# LED_board.net
KiCad netlist of a schematic drawn in EAGLE
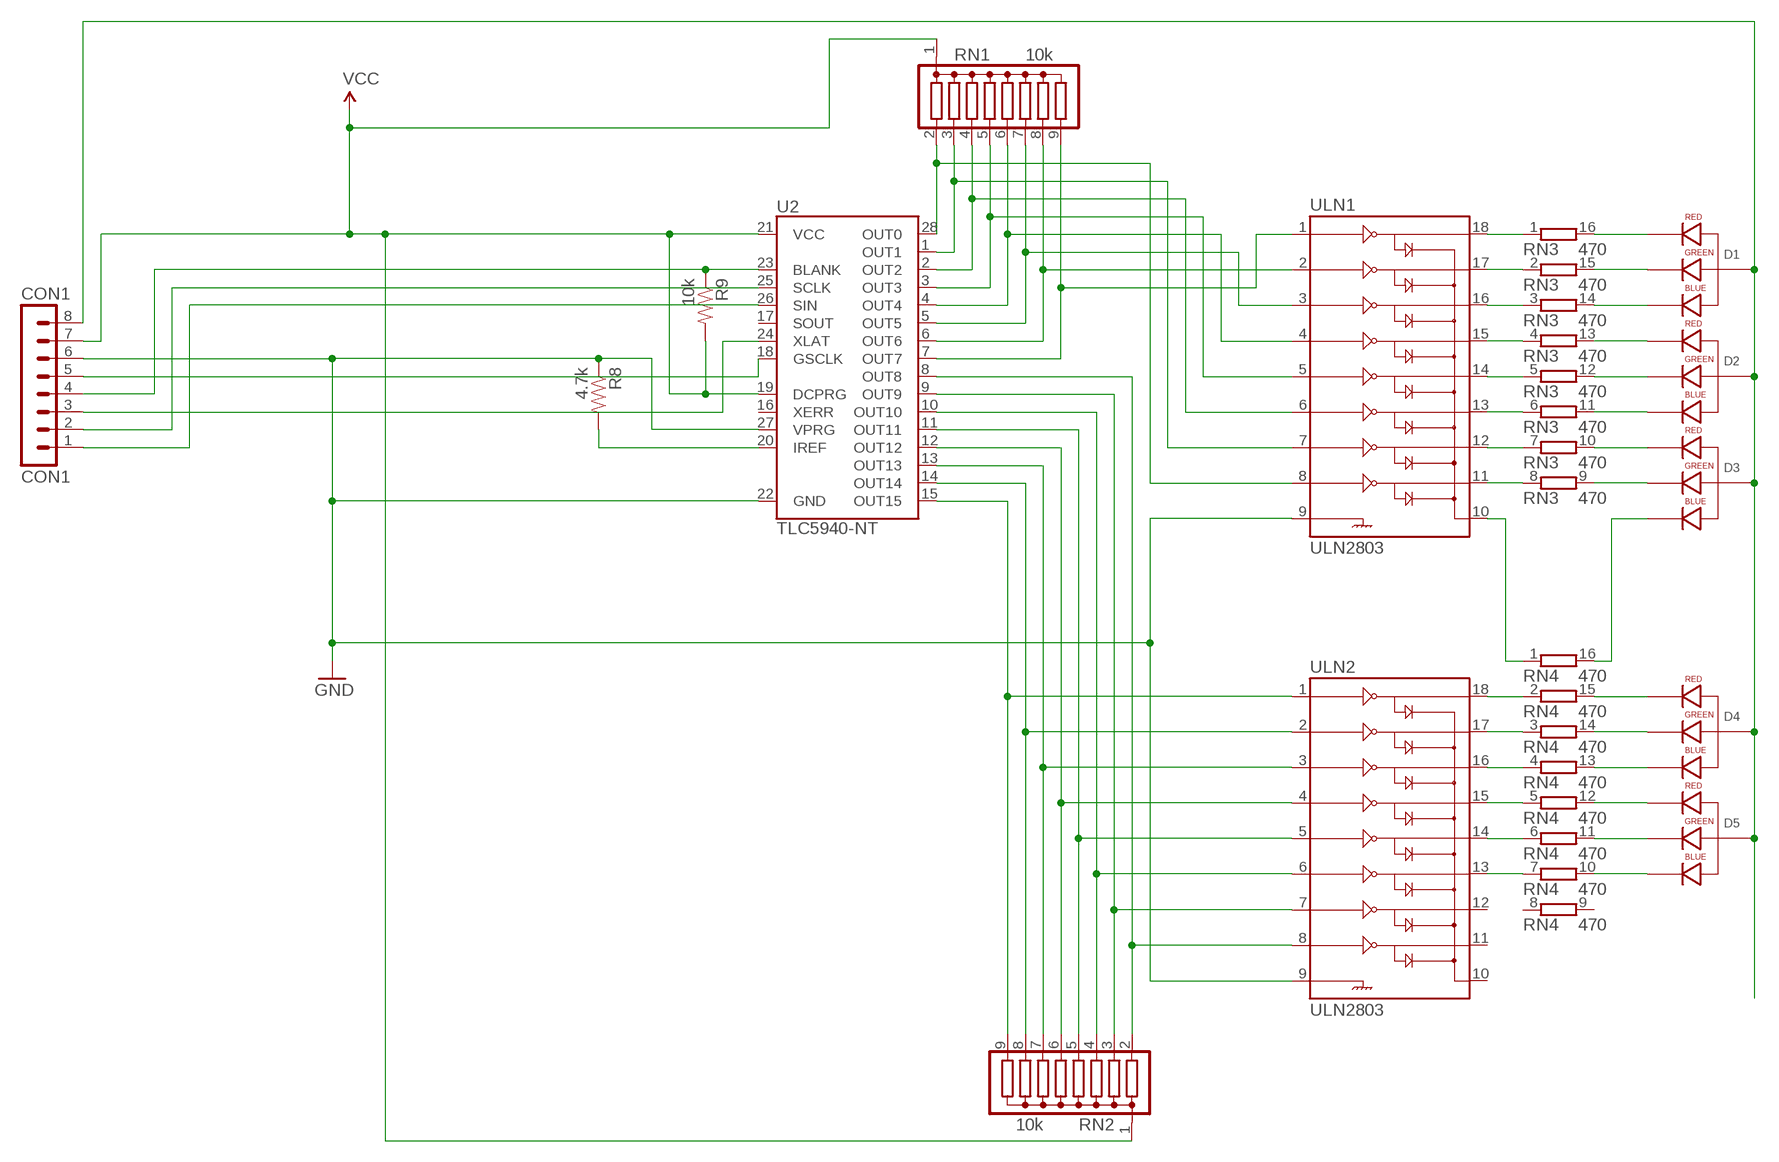
[diagram p0: schematic, sheet 1]

(export (version "E")
  (design (tool "Eeschema 10.0.6"))
  (components
    (comp (ref "CON1")
      (value "CON1")
      (footprint "eagle-import:MA08-1")
      (libsource (lib "eagle-import") (part "MA08-1"))
    )
    (comp (ref "D1")
      (value "LED-RGB-CA-THRUCLEAR")
      (footprint "eagle-import:LED-RGB-THRU")
      (libsource (lib "eagle-import") (part "LED-RGB-CA-THRUCLEAR"))
    )
    (comp (ref "D2")
      (value "LED-RGB-CA-THRUCLEAR")
      (footprint "eagle-import:LED-RGB-THRU")
      (libsource (lib "eagle-import") (part "LED-RGB-CA-THRUCLEAR"))
    )
    (comp (ref "D3")
      (value "LED-RGB-CA-THRUCLEAR")
      (footprint "eagle-import:LED-RGB-THRU")
      (libsource (lib "eagle-import") (part "LED-RGB-CA-THRUCLEAR"))
    )
    (comp (ref "D4")
      (value "LED-RGB-CA-THRUCLEAR")
      (footprint "eagle-import:LED-RGB-THRU")
      (libsource (lib "eagle-import") (part "LED-RGB-CA-THRUCLEAR"))
    )
    (comp (ref "D5")
      (value "LED-RGB-CA-THRUCLEAR")
      (footprint "eagle-import:LED-RGB-THRU")
      (libsource (lib "eagle-import") (part "LED-RGB-CA-THRUCLEAR"))
    )
    (comp (ref "R8")
      (value "4.7k")
      (footprint "eagle-import:AXIAL-0.5")
      (libsource (lib "eagle-import") (part "RESISTORPTH-1/2W"))
    )
    (comp (ref "R9")
      (value "10k")
      (footprint "eagle-import:AXIAL-0.5")
      (libsource (lib "eagle-import") (part "RESISTORPTH-1/2W"))
    )
    (comp (ref "RN1")
      (value "10k")
      (footprint "eagle-import:SIL9")
      (libsource (lib "eagle-import") (part "G08R"))
    )
    (comp (ref "RN2")
      (value "10k")
      (footprint "eagle-import:SIL9")
      (libsource (lib "eagle-import") (part "G08R"))
    )
    (comp (ref "RN3")
      (value "470")
      (footprint "eagle-import:DIL16")
      (libsource (lib "eagle-import") (part "8R-P"))
    )
    (comp (ref "RN4")
      (value "470")
      (footprint "eagle-import:DIL16")
      (libsource (lib "eagle-import") (part "8R-P"))
    )
    (comp (ref "U2")
      (value "TLC5940-NT")
      (footprint "eagle-import:DIL28-3")
      (libsource (lib "eagle-import") (part "TLC5940-NT"))
    )
    (comp (ref "ULN1")
      (value "ULN2803")
      (footprint "eagle-import:DIL18")
      (libsource (lib "eagle-import") (part "ULN2803DIP"))
    )
    (comp (ref "ULN2")
      (value "ULN2803")
      (footprint "eagle-import:DIL18")
      (libsource (lib "eagle-import") (part "ULN2803DIP"))
    )
  )
  (nets
    (net (code "1") (name "GND") (class "Default")
      (node (ref "CON1") (pin "6") (pinfunction "6_6") (pintype "passive"))
      (node (ref "R8") (pin "P$1") (pinfunction "1_P$1") (pintype "passive"))
      (node (ref "U2") (pin "22") (pinfunction "GND_22") (pintype "bidirectional"))
      (node (ref "U2") (pin "27") (pinfunction "VPRG_27") (pintype "bidirectional"))
      (node (ref "ULN1") (pin "9") (pinfunction "9_9") (pintype "bidirectional"))
      (node (ref "ULN2") (pin "9") (pinfunction "9_9") (pintype "bidirectional"))
    )
    (net (code "2") (name "Net-(D1-ANODE)") (class "Default")
      (node (ref "CON1") (pin "8") (pinfunction "8_8") (pintype "passive"))
      (node (ref "D1") (pin "2") (pinfunction "ANODE_2") (pintype "bidirectional"))
      (node (ref "D2") (pin "2") (pinfunction "ANODE_2") (pintype "bidirectional"))
      (node (ref "D3") (pin "2") (pinfunction "ANODE_2") (pintype "bidirectional"))
      (node (ref "D4") (pin "2") (pinfunction "ANODE_2") (pintype "bidirectional"))
      (node (ref "D5") (pin "2") (pinfunction "ANODE_2") (pintype "bidirectional"))
    )
    (net (code "3") (name "Net-(D1-BLUE_CATHODE)") (class "Default")
      (node (ref "D1") (pin "4") (pinfunction "BLUE_CATHODE_4") (pintype "bidirectional"))
      (node (ref "RN3") (pin "14") (pinfunction "2_14") (pintype "passive"))
    )
    (net (code "4") (name "Net-(D1-GREEN_CATHODE)") (class "Default")
      (node (ref "D1") (pin "3") (pinfunction "GREEN_CATHODE_3") (pintype "bidirectional"))
      (node (ref "RN3") (pin "15") (pinfunction "2_15") (pintype "passive"))
    )
    (net (code "5") (name "Net-(D1-RED_CATHODE)") (class "Default")
      (node (ref "D1") (pin "1") (pinfunction "RED_CATHODE_1") (pintype "bidirectional"))
      (node (ref "RN3") (pin "16") (pinfunction "2_16") (pintype "passive"))
    )
    (net (code "6") (name "Net-(D2-BLUE_CATHODE)") (class "Default")
      (node (ref "D2") (pin "4") (pinfunction "BLUE_CATHODE_4") (pintype "bidirectional"))
      (node (ref "RN3") (pin "11") (pinfunction "2_11") (pintype "passive"))
    )
    (net (code "7") (name "Net-(D2-GREEN_CATHODE)") (class "Default")
      (node (ref "D2") (pin "3") (pinfunction "GREEN_CATHODE_3") (pintype "bidirectional"))
      (node (ref "RN3") (pin "12") (pinfunction "2_12") (pintype "passive"))
    )
    (net (code "8") (name "Net-(D2-RED_CATHODE)") (class "Default")
      (node (ref "D2") (pin "1") (pinfunction "RED_CATHODE_1") (pintype "bidirectional"))
      (node (ref "RN3") (pin "13") (pinfunction "2_13") (pintype "passive"))
    )
    (net (code "9") (name "Net-(D3-BLUE_CATHODE)") (class "Default")
      (node (ref "D3") (pin "4") (pinfunction "BLUE_CATHODE_4") (pintype "bidirectional"))
      (node (ref "RN4") (pin "16") (pinfunction "2_16") (pintype "passive"))
    )
    (net (code "10") (name "Net-(D3-GREEN_CATHODE)") (class "Default")
      (node (ref "D3") (pin "3") (pinfunction "GREEN_CATHODE_3") (pintype "bidirectional"))
      (node (ref "RN3") (pin "9") (pinfunction "2_9") (pintype "passive"))
    )
    (net (code "11") (name "Net-(D3-RED_CATHODE)") (class "Default")
      (node (ref "D3") (pin "1") (pinfunction "RED_CATHODE_1") (pintype "bidirectional"))
      (node (ref "RN3") (pin "10") (pinfunction "2_10") (pintype "passive"))
    )
    (net (code "12") (name "Net-(D4-BLUE_CATHODE)") (class "Default")
      (node (ref "D4") (pin "4") (pinfunction "BLUE_CATHODE_4") (pintype "bidirectional"))
      (node (ref "RN4") (pin "13") (pinfunction "2_13") (pintype "passive"))
    )
    (net (code "13") (name "Net-(D4-GREEN_CATHODE)") (class "Default")
      (node (ref "D4") (pin "3") (pinfunction "GREEN_CATHODE_3") (pintype "bidirectional"))
      (node (ref "RN4") (pin "14") (pinfunction "2_14") (pintype "passive"))
    )
    (net (code "14") (name "Net-(D4-RED_CATHODE)") (class "Default")
      (node (ref "D4") (pin "1") (pinfunction "RED_CATHODE_1") (pintype "bidirectional"))
      (node (ref "RN4") (pin "15") (pinfunction "2_15") (pintype "passive"))
    )
    (net (code "15") (name "Net-(D5-BLUE_CATHODE)") (class "Default")
      (node (ref "D5") (pin "4") (pinfunction "BLUE_CATHODE_4") (pintype "bidirectional"))
      (node (ref "RN4") (pin "10") (pinfunction "2_10") (pintype "passive"))
    )
    (net (code "16") (name "Net-(D5-GREEN_CATHODE)") (class "Default")
      (node (ref "D5") (pin "3") (pinfunction "GREEN_CATHODE_3") (pintype "bidirectional"))
      (node (ref "RN4") (pin "11") (pinfunction "2_11") (pintype "passive"))
    )
    (net (code "17") (name "Net-(D5-RED_CATHODE)") (class "Default")
      (node (ref "D5") (pin "1") (pinfunction "RED_CATHODE_1") (pintype "bidirectional"))
      (node (ref "RN4") (pin "12") (pinfunction "2_12") (pintype "passive"))
    )
    (net (code "18") (name "Net-(R8-2)") (class "Default")
      (node (ref "R8") (pin "P$2") (pinfunction "2_P$2") (pintype "passive"))
      (node (ref "U2") (pin "20") (pinfunction "IREF_20") (pintype "bidirectional"))
    )
    (net (code "19") (name "Net-(R9-1)") (class "Default")
      (node (ref "CON1") (pin "4") (pinfunction "4_4") (pintype "passive"))
      (node (ref "R9") (pin "P$1") (pinfunction "1_P$1") (pintype "passive"))
      (node (ref "U2") (pin "23") (pinfunction "BLANK_23") (pintype "bidirectional"))
    )
    (net (code "20") (name "Net-(RN3-Pad1)") (class "Default")
      (node (ref "RN3") (pin "1") (pinfunction "1_1") (pintype "passive"))
      (node (ref "ULN1") (pin "18") (pinfunction "18_18") (pintype "bidirectional"))
    )
    (net (code "21") (name "Net-(RN3B-1)") (class "Default")
      (node (ref "RN3") (pin "2") (pinfunction "1_2") (pintype "passive"))
      (node (ref "ULN1") (pin "17") (pinfunction "17_17") (pintype "bidirectional"))
    )
    (net (code "22") (name "Net-(RN3C-1)") (class "Default")
      (node (ref "RN3") (pin "3") (pinfunction "1_3") (pintype "passive"))
      (node (ref "ULN1") (pin "16") (pinfunction "16_16") (pintype "bidirectional"))
    )
    (net (code "23") (name "Net-(RN3D-1)") (class "Default")
      (node (ref "RN3") (pin "4") (pinfunction "1_4") (pintype "passive"))
      (node (ref "ULN1") (pin "15") (pinfunction "15_15") (pintype "bidirectional"))
    )
    (net (code "24") (name "Net-(RN3E-1)") (class "Default")
      (node (ref "RN3") (pin "5") (pinfunction "1_5") (pintype "passive"))
      (node (ref "ULN1") (pin "14") (pinfunction "14_14") (pintype "bidirectional"))
    )
    (net (code "25") (name "Net-(RN3F-1)") (class "Default")
      (node (ref "RN3") (pin "6") (pinfunction "1_6") (pintype "passive"))
      (node (ref "ULN1") (pin "13") (pinfunction "13_13") (pintype "bidirectional"))
    )
    (net (code "26") (name "Net-(RN3G-1)") (class "Default")
      (node (ref "RN3") (pin "7") (pinfunction "1_7") (pintype "passive"))
      (node (ref "ULN1") (pin "12") (pinfunction "12_12") (pintype "bidirectional"))
    )
    (net (code "27") (name "Net-(RN3H-1)") (class "Default")
      (node (ref "RN3") (pin "8") (pinfunction "1_8") (pintype "passive"))
      (node (ref "ULN1") (pin "11") (pinfunction "11_11") (pintype "bidirectional"))
    )
    (net (code "28") (name "Net-(RN4-Pad1)") (class "Default")
      (node (ref "RN4") (pin "1") (pinfunction "1_1") (pintype "passive"))
      (node (ref "ULN1") (pin "10") (pinfunction "10_10") (pintype "bidirectional"))
    )
    (net (code "29") (name "Net-(RN4B-1)") (class "Default")
      (node (ref "RN4") (pin "2") (pinfunction "1_2") (pintype "passive"))
      (node (ref "ULN2") (pin "18") (pinfunction "18_18") (pintype "bidirectional"))
    )
    (net (code "30") (name "Net-(RN4C-1)") (class "Default")
      (node (ref "RN4") (pin "3") (pinfunction "1_3") (pintype "passive"))
      (node (ref "ULN2") (pin "17") (pinfunction "17_17") (pintype "bidirectional"))
    )
    (net (code "31") (name "Net-(RN4D-1)") (class "Default")
      (node (ref "RN4") (pin "4") (pinfunction "1_4") (pintype "passive"))
      (node (ref "ULN2") (pin "16") (pinfunction "16_16") (pintype "bidirectional"))
    )
    (net (code "32") (name "Net-(RN4E-1)") (class "Default")
      (node (ref "RN4") (pin "5") (pinfunction "1_5") (pintype "passive"))
      (node (ref "ULN2") (pin "15") (pinfunction "15_15") (pintype "bidirectional"))
    )
    (net (code "33") (name "Net-(RN4F-1)") (class "Default")
      (node (ref "RN4") (pin "6") (pinfunction "1_6") (pintype "passive"))
      (node (ref "ULN2") (pin "14") (pinfunction "14_14") (pintype "bidirectional"))
    )
    (net (code "34") (name "Net-(RN4G-1)") (class "Default")
      (node (ref "RN4") (pin "7") (pinfunction "1_7") (pintype "passive"))
      (node (ref "ULN2") (pin "13") (pinfunction "13_13") (pintype "bidirectional"))
    )
    (net (code "35") (name "Net-(U2-GSCLK)") (class "Default")
      (node (ref "CON1") (pin "5") (pinfunction "5_5") (pintype "passive"))
      (node (ref "U2") (pin "18") (pinfunction "GSCLK_18") (pintype "bidirectional"))
    )
    (net (code "36") (name "Net-(U2-OUT0)") (class "Default")
      (node (ref "RN1") (pin "2") (pinfunction "2_2") (pintype "passive"))
      (node (ref "U2") (pin "28") (pinfunction "OUT0_28") (pintype "bidirectional"))
      (node (ref "ULN1") (pin "8") (pinfunction "8_8") (pintype "bidirectional"))
    )
    (net (code "37") (name "Net-(U2-OUT1)") (class "Default")
      (node (ref "RN1") (pin "3") (pinfunction "3_3") (pintype "passive"))
      (node (ref "U2") (pin "1") (pinfunction "OUT1_1") (pintype "bidirectional"))
      (node (ref "ULN1") (pin "7") (pinfunction "7_7") (pintype "bidirectional"))
    )
    (net (code "38") (name "Net-(U2-OUT2)") (class "Default")
      (node (ref "RN1") (pin "4") (pinfunction "4_4") (pintype "passive"))
      (node (ref "U2") (pin "2") (pinfunction "OUT2_2") (pintype "bidirectional"))
      (node (ref "ULN1") (pin "6") (pinfunction "6_6") (pintype "bidirectional"))
    )
    (net (code "39") (name "Net-(U2-OUT3)") (class "Default")
      (node (ref "RN1") (pin "5") (pinfunction "5_5") (pintype "passive"))
      (node (ref "U2") (pin "3") (pinfunction "OUT3_3") (pintype "bidirectional"))
      (node (ref "ULN1") (pin "5") (pinfunction "5_5") (pintype "bidirectional"))
    )
    (net (code "40") (name "Net-(U2-OUT4)") (class "Default")
      (node (ref "RN1") (pin "6") (pinfunction "6_6") (pintype "passive"))
      (node (ref "U2") (pin "4") (pinfunction "OUT4_4") (pintype "bidirectional"))
      (node (ref "ULN1") (pin "4") (pinfunction "4_4") (pintype "bidirectional"))
    )
    (net (code "41") (name "Net-(U2-OUT5)") (class "Default")
      (node (ref "RN1") (pin "7") (pinfunction "7_7") (pintype "passive"))
      (node (ref "U2") (pin "5") (pinfunction "OUT5_5") (pintype "bidirectional"))
      (node (ref "ULN1") (pin "3") (pinfunction "3_3") (pintype "bidirectional"))
    )
    (net (code "42") (name "Net-(U2-OUT6)") (class "Default")
      (node (ref "RN1") (pin "8") (pinfunction "8_8") (pintype "passive"))
      (node (ref "U2") (pin "6") (pinfunction "OUT6_6") (pintype "bidirectional"))
      (node (ref "ULN1") (pin "2") (pinfunction "2_2") (pintype "bidirectional"))
    )
    (net (code "43") (name "Net-(U2-OUT7)") (class "Default")
      (node (ref "RN1") (pin "9") (pinfunction "9_9") (pintype "passive"))
      (node (ref "U2") (pin "7") (pinfunction "OUT7_7") (pintype "bidirectional"))
      (node (ref "ULN1") (pin "1") (pinfunction "1_1") (pintype "bidirectional"))
    )
    (net (code "44") (name "Net-(U2-OUT8)") (class "Default")
      (node (ref "RN2") (pin "2") (pinfunction "2_2") (pintype "passive"))
      (node (ref "U2") (pin "8") (pinfunction "OUT8_8") (pintype "bidirectional"))
      (node (ref "ULN2") (pin "8") (pinfunction "8_8") (pintype "bidirectional"))
    )
    (net (code "45") (name "Net-(U2-OUT9)") (class "Default")
      (node (ref "RN2") (pin "3") (pinfunction "3_3") (pintype "passive"))
      (node (ref "U2") (pin "9") (pinfunction "OUT9_9") (pintype "bidirectional"))
      (node (ref "ULN2") (pin "7") (pinfunction "7_7") (pintype "bidirectional"))
    )
    (net (code "46") (name "Net-(U2-OUT10)") (class "Default")
      (node (ref "RN2") (pin "4") (pinfunction "4_4") (pintype "passive"))
      (node (ref "U2") (pin "10") (pinfunction "OUT10_10") (pintype "bidirectional"))
      (node (ref "ULN2") (pin "6") (pinfunction "6_6") (pintype "bidirectional"))
    )
    (net (code "47") (name "Net-(U2-OUT11)") (class "Default")
      (node (ref "RN2") (pin "5") (pinfunction "5_5") (pintype "passive"))
      (node (ref "U2") (pin "11") (pinfunction "OUT11_11") (pintype "bidirectional"))
      (node (ref "ULN2") (pin "5") (pinfunction "5_5") (pintype "bidirectional"))
    )
    (net (code "48") (name "Net-(U2-OUT12)") (class "Default")
      (node (ref "RN2") (pin "6") (pinfunction "6_6") (pintype "passive"))
      (node (ref "U2") (pin "12") (pinfunction "OUT12_12") (pintype "bidirectional"))
      (node (ref "ULN2") (pin "4") (pinfunction "4_4") (pintype "bidirectional"))
    )
    (net (code "49") (name "Net-(U2-OUT13)") (class "Default")
      (node (ref "RN2") (pin "7") (pinfunction "7_7") (pintype "passive"))
      (node (ref "U2") (pin "13") (pinfunction "OUT13_13") (pintype "bidirectional"))
      (node (ref "ULN2") (pin "3") (pinfunction "3_3") (pintype "bidirectional"))
    )
    (net (code "50") (name "Net-(U2-OUT14)") (class "Default")
      (node (ref "RN2") (pin "8") (pinfunction "8_8") (pintype "passive"))
      (node (ref "U2") (pin "14") (pinfunction "OUT14_14") (pintype "bidirectional"))
      (node (ref "ULN2") (pin "2") (pinfunction "2_2") (pintype "bidirectional"))
    )
    (net (code "51") (name "Net-(U2-OUT15)") (class "Default")
      (node (ref "RN2") (pin "9") (pinfunction "9_9") (pintype "passive"))
      (node (ref "U2") (pin "15") (pinfunction "OUT15_15") (pintype "bidirectional"))
      (node (ref "ULN2") (pin "1") (pinfunction "1_1") (pintype "bidirectional"))
    )
    (net (code "52") (name "Net-(U2-SCLK)") (class "Default")
      (node (ref "CON1") (pin "2") (pinfunction "2_2") (pintype "passive"))
      (node (ref "U2") (pin "25") (pinfunction "SCLK_25") (pintype "bidirectional"))
    )
    (net (code "53") (name "Net-(U2-SIN)") (class "Default")
      (node (ref "CON1") (pin "1") (pinfunction "1_1") (pintype "passive"))
      (node (ref "U2") (pin "26") (pinfunction "SIN_26") (pintype "bidirectional"))
    )
    (net (code "54") (name "Net-(U2-XLAT)") (class "Default")
      (node (ref "CON1") (pin "3") (pinfunction "3_3") (pintype "passive"))
      (node (ref "U2") (pin "24") (pinfunction "XLAT_24") (pintype "bidirectional"))
    )
    (net (code "55") (name "VCC") (class "Default")
      (node (ref "CON1") (pin "7") (pinfunction "7_7") (pintype "passive"))
      (node (ref "R9") (pin "P$2") (pinfunction "2_P$2") (pintype "passive"))
      (node (ref "RN1") (pin "1") (pinfunction "1_1") (pintype "passive"))
      (node (ref "RN2") (pin "1") (pinfunction "1_1") (pintype "passive"))
      (node (ref "U2") (pin "19") (pinfunction "DCPRG_19") (pintype "bidirectional"))
      (node (ref "U2") (pin "21") (pinfunction "VCC_21") (pintype "bidirectional"))
    )
    (net (code "56") (name "unconnected-(RN4H-1-Pad8)") (class "Default")
      (node (ref "RN4") (pin "8") (pinfunction "1_8") (pintype "passive"))
    )
    (net (code "57") (name "unconnected-(RN4H-2-Pad9)") (class "Default")
      (node (ref "RN4") (pin "9") (pinfunction "2_9") (pintype "passive"))
    )
    (net (code "58") (name "unconnected-(U2-SOUT-Pad17)") (class "Default")
      (node (ref "U2") (pin "17") (pinfunction "SOUT_17") (pintype "bidirectional"))
    )
    (net (code "59") (name "unconnected-(U2-XERR-Pad16)") (class "Default")
      (node (ref "U2") (pin "16") (pinfunction "XERR_16") (pintype "bidirectional"))
    )
    (net (code "60") (name "unconnected-(ULN2-Pad10)") (class "Default")
      (node (ref "ULN2") (pin "10") (pinfunction "10_10") (pintype "bidirectional"))
    )
    (net (code "61") (name "unconnected-(ULN2-Pad11)") (class "Default")
      (node (ref "ULN2") (pin "11") (pinfunction "11_11") (pintype "bidirectional"))
    )
    (net (code "62") (name "unconnected-(ULN2-Pad12)") (class "Default")
      (node (ref "ULN2") (pin "12") (pinfunction "12_12") (pintype "bidirectional"))
    )
  )
)
